# base.net
KiCad netlist of a schematic drawn in EAGLE
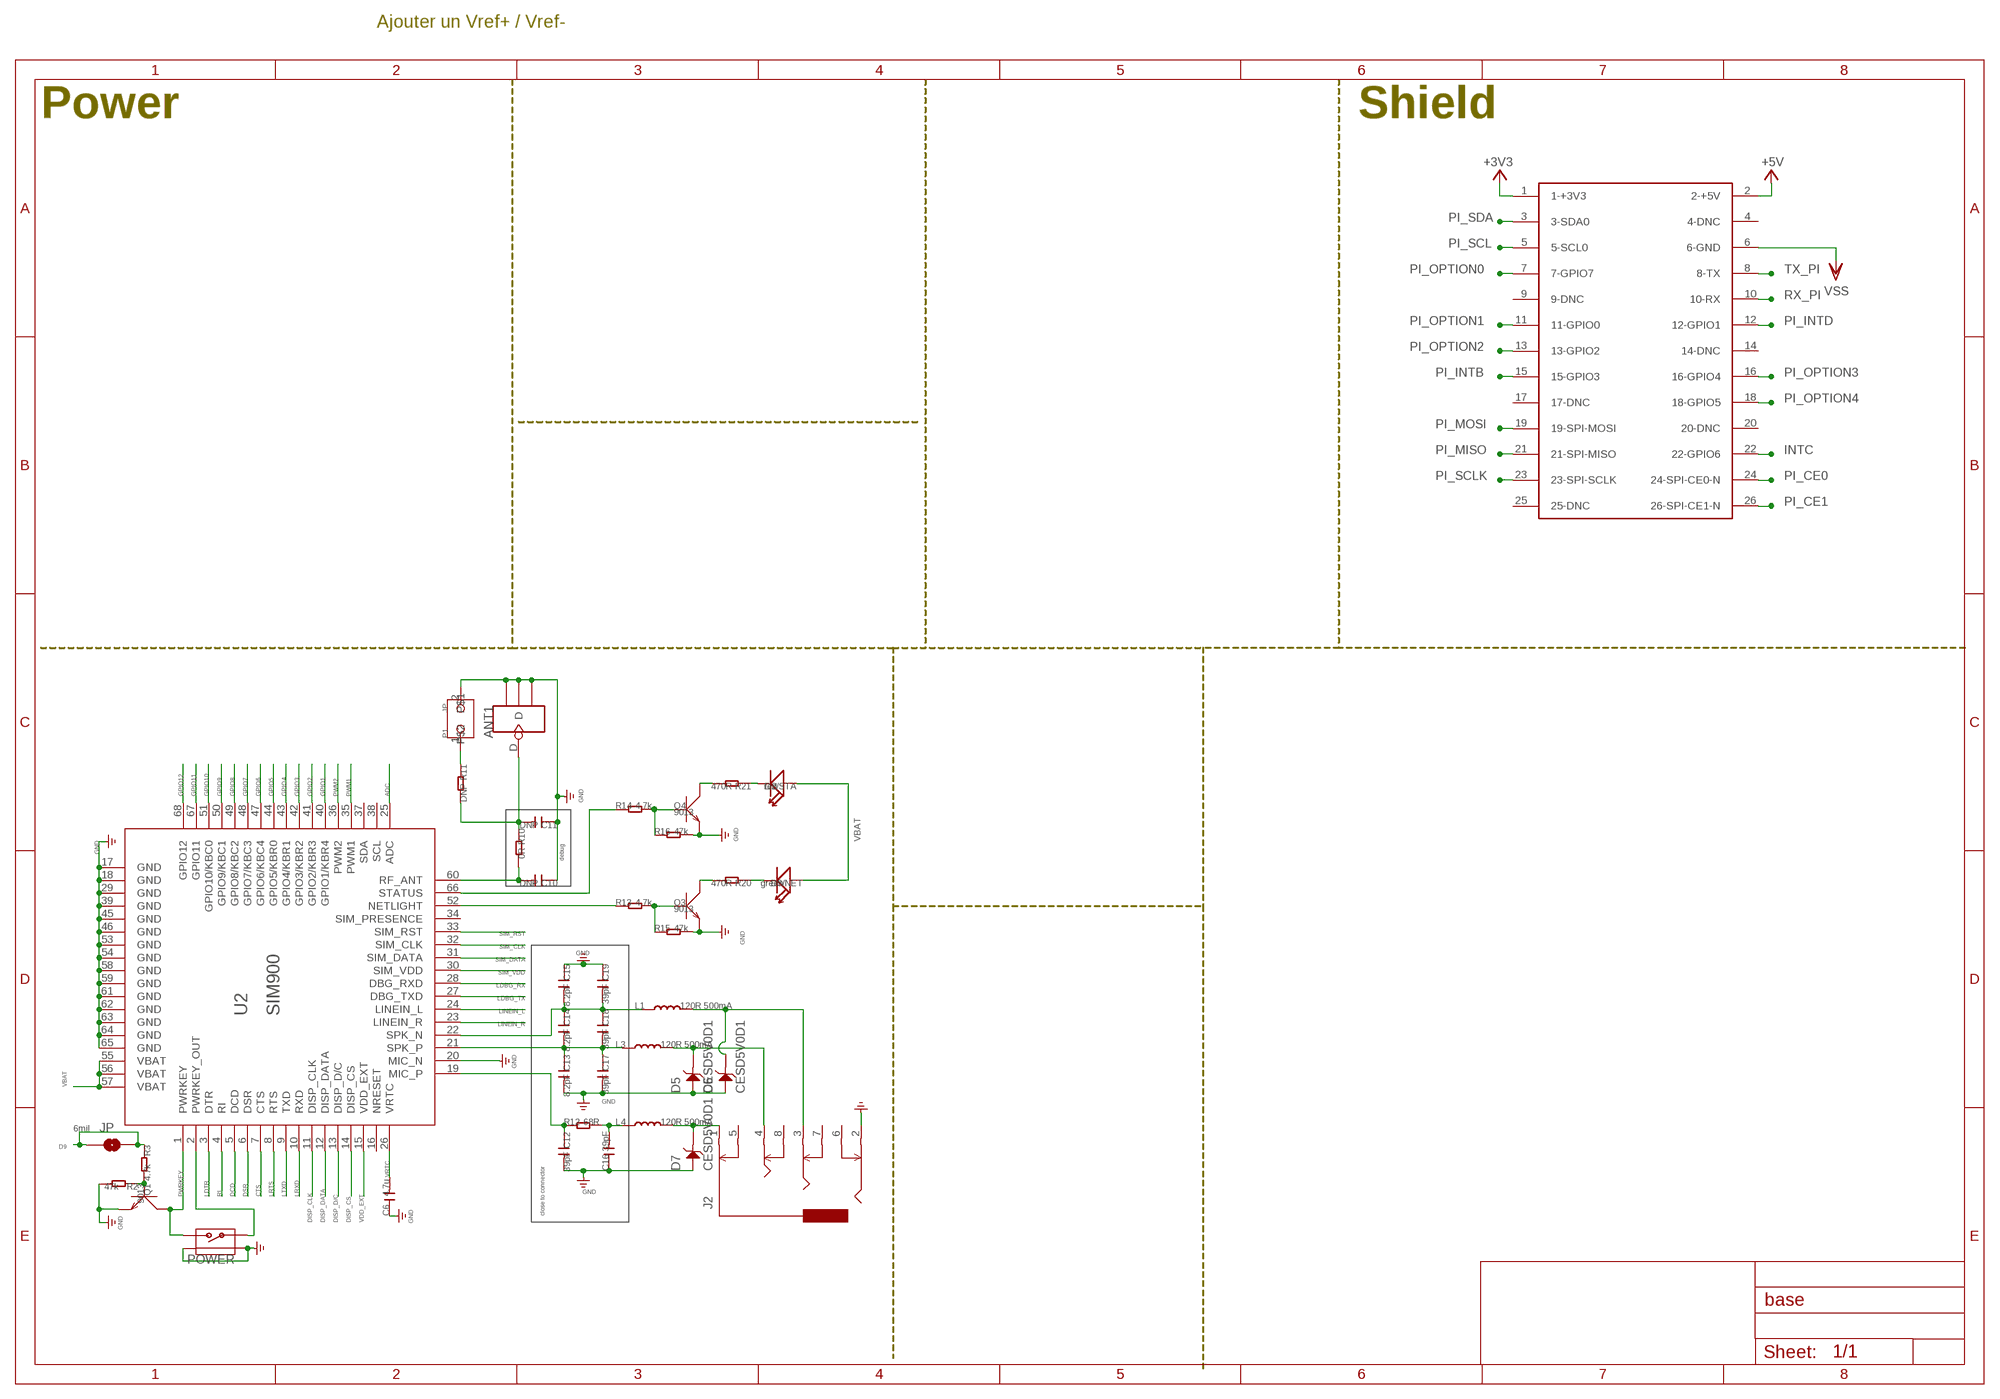
[diagram p0: schematic, sheet 1]

(export (version "E")
  (design (tool "Eeschema 10.0.6"))
  (components
    (comp (ref "ANT1")
      (value "ANTENNA-U-FL")
      (footprint "eagle-import:4P-U-FL")
      (libsource (lib "eagle-import") (part "ANTENNA-U-FL"))
    )
    (comp (ref "C6")
      (value "4.7u")
      (footprint "eagle-import:C0805")
      (libsource (lib "eagle-import") (part "C-0805"))
    )
    (comp (ref "C10")
      (value "DNP")
      (footprint "eagle-import:C0603")
      (libsource (lib "eagle-import") (part "C-0603"))
    )
    (comp (ref "C11")
      (value "DNP")
      (footprint "eagle-import:C0603")
      (libsource (lib "eagle-import") (part "C-0603"))
    )
    (comp (ref "C12")
      (value "39pF")
      (footprint "eagle-import:C0603")
      (libsource (lib "eagle-import") (part "C-0603"))
    )
    (comp (ref "C13")
      (value "8.2pF")
      (footprint "eagle-import:C0603")
      (libsource (lib "eagle-import") (part "C-0603"))
    )
    (comp (ref "C14")
      (value "8.2pF")
      (footprint "eagle-import:C0603")
      (libsource (lib "eagle-import") (part "C-0603"))
    )
    (comp (ref "C15")
      (value "8.2pF")
      (footprint "eagle-import:C0603")
      (libsource (lib "eagle-import") (part "C-0603"))
    )
    (comp (ref "C16")
      (value "39pF")
      (footprint "eagle-import:C0603")
      (libsource (lib "eagle-import") (part "C-0603"))
    )
    (comp (ref "C17")
      (value "39pF")
      (footprint "eagle-import:C0603")
      (libsource (lib "eagle-import") (part "C-0603"))
    )
    (comp (ref "C18")
      (value "39pF")
      (footprint "eagle-import:C0603")
      (libsource (lib "eagle-import") (part "C-0603"))
    )
    (comp (ref "C19")
      (value "39pF")
      (footprint "eagle-import:C0603")
      (libsource (lib "eagle-import") (part "C-0603"))
    )
    (comp (ref "D2/STA")
      (value "red")
      (footprint "eagle-import:LED-0603")
      (libsource (lib "eagle-import") (part "LED'0603'"))
    )
    (comp (ref "D3/NET")
      (value "green")
      (footprint "eagle-import:LED-0603")
      (libsource (lib "eagle-import") (part "LED'0603'"))
    )
    (comp (ref "D5")
      (value "CESD5V0D1")
      (footprint "eagle-import:SOD123-2.7X1.6")
      (libsource (lib "eagle-import") (part "D-ESD"))
    )
    (comp (ref "D6")
      (value "CESD5V0D1")
      (footprint "eagle-import:SOD123-2.7X1.6")
      (libsource (lib "eagle-import") (part "D-ESD"))
    )
    (comp (ref "D7")
      (value "CESD5V0D1")
      (footprint "eagle-import:SOD123-2.7X1.6")
      (libsource (lib "eagle-import") (part "D-ESD"))
    )
    (comp (ref "J2")
      (value "AUDIO-8P'PJ-3536-L6S'")
      (footprint "eagle-import:8P-3.5-SMD")
      (libsource (lib "eagle-import") (part "AUDIO-8P'PJ-3536-L6S'"))
    )
    (comp (ref "JP")
      (value "PAD-SOLDERJUMPERNC")
      (footprint "eagle-import:2P-SMD-3.3X2")
      (libsource (lib "eagle-import") (part "PAD-SOLDERJUMPERNC"))
    )
    (comp (ref "L1")
      (value "120R 500mA")
      (footprint "eagle-import:L0603")
      (libsource (lib "eagle-import") (part "L'0603'"))
    )
    (comp (ref "L3")
      (value "120R 500mA")
      (footprint "eagle-import:L0603")
      (libsource (lib "eagle-import") (part "L'0603'"))
    )
    (comp (ref "L4")
      (value "120R 500mA")
      (footprint "eagle-import:L0603")
      (libsource (lib "eagle-import") (part "L'0603'"))
    )
    (comp (ref "P1") (value "JP") (footprint "eagle-import:JP") (libsource (lib "eagle-import") (part "JP")))
    (comp (ref "POWER")
      (value "BUTTON-4P-REINFORCE'TS-118E'")
      (footprint "eagle-import:4P-SMD-7X3.5X3.5H")
      (libsource (lib "eagle-import") (part "BUTTON-4P-REINFORCE'TS-118E'"))
    )
    (comp (ref "Q1")
      (value "9013")
      (footprint "eagle-import:SOT23")
      (libsource (lib "eagle-import") (part "TRANSISTOR-NPN-SOT23"))
    )
    (comp (ref "Q3")
      (value "9013")
      (footprint "eagle-import:SOT23")
      (libsource (lib "eagle-import") (part "TRANSISTOR-NPN-SOT23"))
    )
    (comp (ref "Q4")
      (value "9013")
      (footprint "eagle-import:SOT23")
      (libsource (lib "eagle-import") (part "TRANSISTOR-NPN-SOT23"))
    )
    (comp (ref "R2")
      (value "47k")
      (footprint "eagle-import:R0603")
      (libsource (lib "eagle-import") (part "R-0603"))
    )
    (comp (ref "R3")
      (value "4.7k")
      (footprint "eagle-import:R0603")
      (libsource (lib "eagle-import") (part "R-0603"))
    )
    (comp (ref "R10")
      (value "0R")
      (footprint "eagle-import:R0603")
      (libsource (lib "eagle-import") (part "R-0603"))
    )
    (comp (ref "R11")
      (value "DNP")
      (footprint "eagle-import:R0603")
      (libsource (lib "eagle-import") (part "R-0603"))
    )
    (comp (ref "R12")
      (value "68R")
      (footprint "eagle-import:R0603")
      (libsource (lib "eagle-import") (part "R-0603"))
    )
    (comp (ref "R13")
      (value "4.7k")
      (footprint "eagle-import:R0603")
      (libsource (lib "eagle-import") (part "R-0603"))
    )
    (comp (ref "R14")
      (value "4.7k")
      (footprint "eagle-import:R0603")
      (libsource (lib "eagle-import") (part "R-0603"))
    )
    (comp (ref "R15")
      (value "47k")
      (footprint "eagle-import:R0603")
      (libsource (lib "eagle-import") (part "R-0603"))
    )
    (comp (ref "R16")
      (value "47k")
      (footprint "eagle-import:R0603")
      (libsource (lib "eagle-import") (part "R-0603"))
    )
    (comp (ref "R20")
      (value "470R")
      (footprint "eagle-import:R0603")
      (libsource (lib "eagle-import") (part "R-0603"))
    )
    (comp (ref "R21")
      (value "470R")
      (footprint "eagle-import:R0603")
      (libsource (lib "eagle-import") (part "R-0603"))
    )
    (comp (ref "U$3")
      (value "RASPBERRY-PILIGHT-HOLE")
      (footprint "eagle-import:RASPBERRY-PI-LIGHT-HOLE")
      (libsource (lib "eagle-import") (part "RASPBERRY-PILIGHT-HOLE"))
    )
    (comp (ref "U2")
      (value "SIM900")
      (footprint "eagle-import:SIM900")
      (libsource (lib "eagle-import") (part "SIM900"))
    )
  )
  (nets
    (net (code "1") (name "+3V3") (class "Default")
      (node (ref "U$3") (pin "1") (pinfunction "1-+3V3_1") (pintype "bidirectional"))
    )
    (net (code "2") (name "+5V") (class "Default")
      (node (ref "U$3") (pin "2") (pinfunction "2-+5V_2") (pintype "bidirectional"))
    )
    (net (code "3") (name "/ADC") (class "Default")
      (node (ref "U2") (pin "25") (pinfunction "ADC_25") (pintype "input"))
    )
    (net (code "4") (name "/CTS") (class "Default")
      (node (ref "U2") (pin "7") (pinfunction "CTS_7") (pintype "output"))
    )
    (net (code "5") (name "/D9") (class "Default")
      (node (ref "JP") (pin "1") (pinfunction "1_1") (pintype "passive"))
      (node (ref "JP") (pin "2") (pinfunction "2_2") (pintype "passive"))
      (node (ref "R3") (pin "1") (pinfunction "1_1") (pintype "passive"))
    )
    (net (code "6") (name "/DCD") (class "Default")
      (node (ref "U2") (pin "5") (pinfunction "DCD_5") (pintype "output"))
    )
    (net (code "7") (name "/DISP_CLK") (class "Default")
      (node (ref "U2") (pin "11") (pinfunction "DISP_CLK_11") (pintype "output"))
    )
    (net (code "8") (name "/DISP_CS") (class "Default")
      (node (ref "U2") (pin "14") (pinfunction "DISP_CS_14") (pintype "output"))
    )
    (net (code "9") (name "/DISP_DATA") (class "Default")
      (node (ref "U2") (pin "12") (pinfunction "DISP_DATA_12") (pintype "bidirectional"))
    )
    (net (code "10") (name "/DISP_D{slash}C") (class "Default")
      (node (ref "U2") (pin "13") (pinfunction "DISP_D/C_13") (pintype "output"))
    )
    (net (code "11") (name "/DSR") (class "Default")
      (node (ref "U2") (pin "6") (pinfunction "DSR_6") (pintype "output"))
    )
    (net (code "12") (name "/GPIO1") (class "Default")
      (node (ref "U2") (pin "40") (pinfunction "GPIO1/KBR4_40") (pintype "output"))
    )
    (net (code "13") (name "/GPIO2") (class "Default")
      (node (ref "U2") (pin "41") (pinfunction "GPIO2/KBR3_41") (pintype "output"))
    )
    (net (code "14") (name "/GPIO3") (class "Default")
      (node (ref "U2") (pin "42") (pinfunction "GPIO3/KBR2_42") (pintype "output"))
    )
    (net (code "15") (name "/GPIO4") (class "Default")
      (node (ref "U2") (pin "43") (pinfunction "GPIO4/KBR1_43") (pintype "output"))
    )
    (net (code "16") (name "/GPIO5") (class "Default")
      (node (ref "U2") (pin "44") (pinfunction "GPIO5/KBR0_44") (pintype "output"))
    )
    (net (code "17") (name "/GPIO6") (class "Default")
      (node (ref "U2") (pin "47") (pinfunction "GPIO6/KBC4_47") (pintype "input"))
    )
    (net (code "18") (name "/GPIO7") (class "Default")
      (node (ref "U2") (pin "48") (pinfunction "GPIO7/KBC3_48") (pintype "bidirectional"))
    )
    (net (code "19") (name "/GPIO8") (class "Default")
      (node (ref "U2") (pin "49") (pinfunction "GPIO8/KBC2_49") (pintype "input"))
    )
    (net (code "20") (name "/GPIO9") (class "Default")
      (node (ref "U2") (pin "50") (pinfunction "GPIO9/KBC1_50") (pintype "input"))
    )
    (net (code "21") (name "/GPIO10") (class "Default")
      (node (ref "U2") (pin "51") (pinfunction "GPIO10/KBC0_51") (pintype "bidirectional"))
    )
    (net (code "22") (name "/GPIO11") (class "Default")
      (node (ref "U2") (pin "67") (pinfunction "GPIO11_67") (pintype "bidirectional"))
    )
    (net (code "23") (name "/GPIO12") (class "Default")
      (node (ref "U2") (pin "68") (pinfunction "GPIO12_68") (pintype "bidirectional"))
    )
    (net (code "24") (name "/INTC") (class "Default")
      (node (ref "U$3") (pin "22") (pinfunction "22-GPIO6_22") (pintype "bidirectional"))
    )
    (net (code "25") (name "/LDBG_RX") (class "Default")
      (node (ref "U2") (pin "28") (pinfunction "DBG_RXD_28") (pintype "input"))
    )
    (net (code "26") (name "/LDBG_TX") (class "Default")
      (node (ref "U2") (pin "27") (pinfunction "DBG_TXD_27") (pintype "output"))
    )
    (net (code "27") (name "/LDTR") (class "Default")
      (node (ref "U2") (pin "3") (pinfunction "DTR_3") (pintype "input"))
    )
    (net (code "28") (name "/LINEIN_L") (class "Default")
      (node (ref "U2") (pin "24") (pinfunction "LINEIN_L_24") (pintype "input"))
    )
    (net (code "29") (name "/LINEIN_R") (class "Default")
      (node (ref "U2") (pin "23") (pinfunction "LINEIN_R_23") (pintype "input"))
    )
    (net (code "30") (name "/LRTS") (class "Default")
      (node (ref "U2") (pin "8") (pinfunction "RTS_8") (pintype "input"))
    )
    (net (code "31") (name "/LRXD") (class "Default")
      (node (ref "U2") (pin "10") (pinfunction "RXD_10") (pintype "input"))
    )
    (net (code "32") (name "/LTXD") (class "Default")
      (node (ref "U2") (pin "9") (pinfunction "TXD_9") (pintype "output"))
    )
    (net (code "33") (name "/PI_CE0") (class "Default")
      (node (ref "U$3") (pin "24") (pinfunction "24-SPI-CE0-N_24") (pintype "bidirectional"))
    )
    (net (code "34") (name "/PI_CE1") (class "Default")
      (node (ref "U$3") (pin "26") (pinfunction "26-SPI-CE1-N_26") (pintype "bidirectional"))
    )
    (net (code "35") (name "/PI_INTB") (class "Default")
      (node (ref "U$3") (pin "15") (pinfunction "15-GPIO3_15") (pintype "bidirectional"))
    )
    (net (code "36") (name "/PI_INTD") (class "Default")
      (node (ref "U$3") (pin "12") (pinfunction "12-GPIO1_12") (pintype "bidirectional"))
    )
    (net (code "37") (name "/PI_MISO") (class "Default")
      (node (ref "U$3") (pin "21") (pinfunction "21-SPI-MISO_21") (pintype "bidirectional"))
    )
    (net (code "38") (name "/PI_MOSI") (class "Default")
      (node (ref "U$3") (pin "19") (pinfunction "19-SPI-MOSI_19") (pintype "bidirectional"))
    )
    (net (code "39") (name "/PI_OPTION0") (class "Default")
      (node (ref "U$3") (pin "7") (pinfunction "7-GPIO7_7") (pintype "bidirectional"))
    )
    (net (code "40") (name "/PI_OPTION1") (class "Default")
      (node (ref "U$3") (pin "11") (pinfunction "11-GPIO0_11") (pintype "bidirectional"))
    )
    (net (code "41") (name "/PI_OPTION2") (class "Default")
      (node (ref "U$3") (pin "13") (pinfunction "13-GPIO2_13") (pintype "bidirectional"))
    )
    (net (code "42") (name "/PI_OPTION3") (class "Default")
      (node (ref "U$3") (pin "16") (pinfunction "16-GPIO4_16") (pintype "bidirectional"))
    )
    (net (code "43") (name "/PI_OPTION4") (class "Default")
      (node (ref "U$3") (pin "18") (pinfunction "18-GPIO5_18") (pintype "bidirectional"))
    )
    (net (code "44") (name "/PI_SCL") (class "Default")
      (node (ref "U$3") (pin "5") (pinfunction "5-SCL0_5") (pintype "bidirectional"))
    )
    (net (code "45") (name "/PI_SCLK") (class "Default")
      (node (ref "U$3") (pin "23") (pinfunction "23-SPI-SCLK_23") (pintype "bidirectional"))
    )
    (net (code "46") (name "/PI_SDA") (class "Default")
      (node (ref "U$3") (pin "3") (pinfunction "3-SDA0_3") (pintype "bidirectional"))
    )
    (net (code "47") (name "/PWM1") (class "Default")
      (node (ref "U2") (pin "35") (pinfunction "PWM1_35") (pintype "output"))
    )
    (net (code "48") (name "/PWM2") (class "Default")
      (node (ref "U2") (pin "36") (pinfunction "PWM2_36") (pintype "output"))
    )
    (net (code "49") (name "/PWRKEY") (class "Default")
      (node (ref "POWER") (pin "2") (pinfunction "2_2") (pintype "bidirectional"))
      (node (ref "Q1") (pin "3") (pinfunction "C_3") (pintype "passive"))
      (node (ref "U2") (pin "1") (pinfunction "PWRKEY_1") (pintype "input"))
    )
    (net (code "50") (name "/RI") (class "Default")
      (node (ref "U2") (pin "4") (pinfunction "RI_4") (pintype "output"))
    )
    (net (code "51") (name "/RX_PI") (class "Default")
      (node (ref "U$3") (pin "10") (pinfunction "10-RX_10") (pintype "bidirectional"))
    )
    (net (code "52") (name "/SIM_CLK") (class "Default")
      (node (ref "U2") (pin "32") (pinfunction "SIM_CLK_32") (pintype "output"))
    )
    (net (code "53") (name "/SIM_DATA") (class "Default")
      (node (ref "U2") (pin "31") (pinfunction "SIM_DATA_31") (pintype "bidirectional"))
    )
    (net (code "54") (name "/SIM_RST") (class "Default")
      (node (ref "U2") (pin "33") (pinfunction "SIM_RST_33") (pintype "output"))
    )
    (net (code "55") (name "/SIM_VDD") (class "Default")
      (node (ref "U2") (pin "30") (pinfunction "SIM_VDD_30") (pintype "output"))
    )
    (net (code "56") (name "/TX_PI") (class "Default")
      (node (ref "U$3") (pin "8") (pinfunction "8-TX_8") (pintype "bidirectional"))
    )
    (net (code "57") (name "/VBAT") (class "Default")
      (node (ref "D2/STA") (pin "+") (pinfunction "+_+") (pintype "passive"))
      (node (ref "D3/NET") (pin "+") (pinfunction "+_+") (pintype "passive"))
      (node (ref "U2") (pin "55") (pinfunction "VBAT_55") (pintype "power_in"))
      (node (ref "U2") (pin "56") (pinfunction "VBAT_56") (pintype "power_in"))
      (node (ref "U2") (pin "57") (pinfunction "VBAT_57") (pintype "power_in"))
    )
    (net (code "58") (name "/VDD_EXT") (class "Default")
      (node (ref "U2") (pin "15") (pinfunction "VDD_EXT_15") (pintype "output"))
    )
    (net (code "59") (name "/VRTC") (class "Default")
      (node (ref "C6") (pin "2") (pinfunction "2_2") (pintype "passive"))
      (node (ref "U2") (pin "26") (pinfunction "VRTC_26") (pintype "bidirectional"))
    )
    (net (code "60") (name "GND_POWER") (class "Default")
      (node (ref "ANT1") (pin "GND1") (pinfunction "GND1_GND1") (pintype "bidirectional"))
      (node (ref "ANT1") (pin "GND2") (pinfunction "GND2_GND2") (pintype "bidirectional"))
      (node (ref "ANT1") (pin "GND3") (pinfunction "GND3_GND3") (pintype "bidirectional"))
      (node (ref "C10") (pin "1") (pinfunction "1_1") (pintype "passive"))
      (node (ref "C11") (pin "1") (pinfunction "1_1") (pintype "passive"))
      (node (ref "C12") (pin "2") (pinfunction "2_2") (pintype "passive"))
      (node (ref "C13") (pin "2") (pinfunction "2_2") (pintype "passive"))
      (node (ref "C15") (pin "1") (pinfunction "1_1") (pintype "passive"))
      (node (ref "C16") (pin "1") (pinfunction "1_1") (pintype "passive"))
      (node (ref "C17") (pin "2") (pinfunction "2_2") (pintype "passive"))
      (node (ref "C19") (pin "1") (pinfunction "1_1") (pintype "passive"))
      (node (ref "C6") (pin "1") (pinfunction "1_1") (pintype "passive"))
      (node (ref "D5") (pin "1") (pinfunction "1_1") (pintype "bidirectional"))
      (node (ref "D6") (pin "1") (pinfunction "1_1") (pintype "bidirectional"))
      (node (ref "D7") (pin "1") (pinfunction "1_1") (pintype "bidirectional"))
      (node (ref "J2") (pin "2") (pinfunction "2_2") (pintype "bidirectional"))
      (node (ref "P1") (pin "2") (pinfunction "P$2_2") (pintype "bidirectional"))
      (node (ref "POWER") (pin "S1") (pinfunction "S1_S1") (pintype "bidirectional"))
      (node (ref "POWER") (pin "S2") (pinfunction "S2_S2") (pintype "bidirectional"))
      (node (ref "Q1") (pin "2") (pinfunction "E_2") (pintype "passive"))
      (node (ref "Q3") (pin "2") (pinfunction "E_2") (pintype "passive"))
      (node (ref "Q4") (pin "2") (pinfunction "E_2") (pintype "passive"))
      (node (ref "R15") (pin "2") (pinfunction "2_2") (pintype "passive"))
      (node (ref "R16") (pin "2") (pinfunction "2_2") (pintype "passive"))
      (node (ref "R2") (pin "2") (pinfunction "2_2") (pintype "passive"))
      (node (ref "U2") (pin "17") (pinfunction "GND_17") (pintype "power_in"))
      (node (ref "U2") (pin "18") (pinfunction "GND_18") (pintype "power_in"))
      (node (ref "U2") (pin "20") (pinfunction "MIC_N_20") (pintype "input"))
      (node (ref "U2") (pin "29") (pinfunction "GND_29") (pintype "power_in"))
      (node (ref "U2") (pin "39") (pinfunction "GND_39") (pintype "power_in"))
      (node (ref "U2") (pin "45") (pinfunction "GND_45") (pintype "power_in"))
      (node (ref "U2") (pin "46") (pinfunction "GND_46") (pintype "power_in"))
      (node (ref "U2") (pin "53") (pinfunction "GND_53") (pintype "power_in"))
      (node (ref "U2") (pin "54") (pinfunction "GND_54") (pintype "power_in"))
      (node (ref "U2") (pin "58") (pinfunction "GND_58") (pintype "power_in"))
      (node (ref "U2") (pin "59") (pinfunction "GND_59") (pintype "power_in"))
      (node (ref "U2") (pin "61") (pinfunction "GND_61") (pintype "power_in"))
      (node (ref "U2") (pin "62") (pinfunction "GND_62") (pintype "power_in"))
      (node (ref "U2") (pin "63") (pinfunction "GND_63") (pintype "power_in"))
      (node (ref "U2") (pin "64") (pinfunction "GND_64") (pintype "power_in"))
      (node (ref "U2") (pin "65") (pinfunction "GND_65") (pintype "power_in"))
    )
    (net (code "61") (name "Net-(ANT1-PadD)") (class "Default")
      (node (ref "ANT1") (pin "D") (pinfunction "D_D") (pintype "bidirectional"))
      (node (ref "C11") (pin "2") (pinfunction "2_2") (pintype "passive"))
      (node (ref "R10") (pin "1") (pinfunction "1_1") (pintype "passive"))
      (node (ref "R11") (pin "2") (pinfunction "2_2") (pintype "passive"))
    )
    (net (code "62") (name "Net-(C16-Pad2)") (class "Default")
      (node (ref "C16") (pin "2") (pinfunction "2_2") (pintype "passive"))
      (node (ref "L4") (pin "1") (pinfunction "1_1") (pintype "passive"))
      (node (ref "R12") (pin "2") (pinfunction "2_2") (pintype "passive"))
    )
    (net (code "63") (name "Net-(D2/STA-Pad-)") (class "Default")
      (node (ref "D2/STA") (pin "-") (pinfunction "-_-") (pintype "passive"))
      (node (ref "R21") (pin "1") (pinfunction "1_1") (pintype "passive"))
    )
    (net (code "64") (name "Net-(D3/NET-Pad-)") (class "Default")
      (node (ref "D3/NET") (pin "-") (pinfunction "-_-") (pintype "passive"))
      (node (ref "R20") (pin "1") (pinfunction "1_1") (pintype "passive"))
    )
    (net (code "65") (name "Net-(D5-Pad2)") (class "Default")
      (node (ref "D5") (pin "2") (pinfunction "2_2") (pintype "bidirectional"))
      (node (ref "J2") (pin "4") (pinfunction "4_4") (pintype "bidirectional"))
      (node (ref "L3") (pin "2") (pinfunction "2_2") (pintype "passive"))
    )
    (net (code "66") (name "Net-(D6-Pad2)") (class "Default")
      (node (ref "D6") (pin "2") (pinfunction "2_2") (pintype "bidirectional"))
      (node (ref "J2") (pin "3") (pinfunction "3_3") (pintype "bidirectional"))
      (node (ref "L1") (pin "2") (pinfunction "2_2") (pintype "passive"))
    )
    (net (code "67") (name "Net-(D7-Pad2)") (class "Default")
      (node (ref "D7") (pin "2") (pinfunction "2_2") (pintype "bidirectional"))
      (node (ref "J2") (pin "1") (pinfunction "1_1") (pintype "bidirectional"))
      (node (ref "L4") (pin "2") (pinfunction "2_2") (pintype "passive"))
    )
    (net (code "68") (name "Net-(P1-P$1)") (class "Default")
      (node (ref "P1") (pin "1") (pinfunction "P$1_1") (pintype "bidirectional"))
      (node (ref "R11") (pin "1") (pinfunction "1_1") (pintype "passive"))
    )
    (net (code "69") (name "Net-(Q1-B)") (class "Default")
      (node (ref "Q1") (pin "1") (pinfunction "B_1") (pintype "passive"))
      (node (ref "R2") (pin "1") (pinfunction "1_1") (pintype "passive"))
      (node (ref "R3") (pin "2") (pinfunction "2_2") (pintype "passive"))
    )
    (net (code "70") (name "Net-(Q3-B)") (class "Default")
      (node (ref "Q3") (pin "1") (pinfunction "B_1") (pintype "passive"))
      (node (ref "R13") (pin "2") (pinfunction "2_2") (pintype "passive"))
      (node (ref "R15") (pin "1") (pinfunction "1_1") (pintype "passive"))
    )
    (net (code "71") (name "Net-(Q3-C)") (class "Default")
      (node (ref "Q3") (pin "3") (pinfunction "C_3") (pintype "passive"))
      (node (ref "R20") (pin "2") (pinfunction "2_2") (pintype "passive"))
    )
    (net (code "72") (name "Net-(Q4-B)") (class "Default")
      (node (ref "Q4") (pin "1") (pinfunction "B_1") (pintype "passive"))
      (node (ref "R14") (pin "2") (pinfunction "2_2") (pintype "passive"))
      (node (ref "R16") (pin "1") (pinfunction "1_1") (pintype "passive"))
    )
    (net (code "73") (name "Net-(Q4-C)") (class "Default")
      (node (ref "Q4") (pin "3") (pinfunction "C_3") (pintype "passive"))
      (node (ref "R21") (pin "2") (pinfunction "2_2") (pintype "passive"))
    )
    (net (code "74") (name "Net-(U2-MIC_P)") (class "Default")
      (node (ref "C12") (pin "1") (pinfunction "1_1") (pintype "passive"))
      (node (ref "R12") (pin "1") (pinfunction "1_1") (pintype "passive"))
      (node (ref "U2") (pin "19") (pinfunction "MIC_P_19") (pintype "input"))
    )
    (net (code "75") (name "Net-(U2-NETLIGHT)") (class "Default")
      (node (ref "R13") (pin "1") (pinfunction "1_1") (pintype "passive"))
      (node (ref "U2") (pin "52") (pinfunction "NETLIGHT_52") (pintype "output"))
    )
    (net (code "76") (name "Net-(U2-PWRKEY_OUT)") (class "Default")
      (node (ref "POWER") (pin "1") (pinfunction "1_1") (pintype "bidirectional"))
      (node (ref "U2") (pin "2") (pinfunction "PWRKEY_OUT_2") (pintype "output"))
    )
    (net (code "77") (name "Net-(U2-RF_ANT)") (class "Default")
      (node (ref "C10") (pin "2") (pinfunction "2_2") (pintype "passive"))
      (node (ref "R10") (pin "2") (pinfunction "2_2") (pintype "passive"))
      (node (ref "U2") (pin "60") (pinfunction "RF_ANT_60") (pintype "bidirectional"))
    )
    (net (code "78") (name "Net-(U2-SPK_N)") (class "Default")
      (node (ref "C14") (pin "1") (pinfunction "1_1") (pintype "passive"))
      (node (ref "C15") (pin "2") (pinfunction "2_2") (pintype "passive"))
      (node (ref "C18") (pin "1") (pinfunction "1_1") (pintype "passive"))
      (node (ref "C19") (pin "2") (pinfunction "2_2") (pintype "passive"))
      (node (ref "L1") (pin "1") (pinfunction "1_1") (pintype "passive"))
      (node (ref "U2") (pin "22") (pinfunction "SPK_N_22") (pintype "output"))
    )
    (net (code "79") (name "Net-(U2-SPK_P)") (class "Default")
      (node (ref "C13") (pin "1") (pinfunction "1_1") (pintype "passive"))
      (node (ref "C14") (pin "2") (pinfunction "2_2") (pintype "passive"))
      (node (ref "C17") (pin "1") (pinfunction "1_1") (pintype "passive"))
      (node (ref "C18") (pin "2") (pinfunction "2_2") (pintype "passive"))
      (node (ref "L3") (pin "1") (pinfunction "1_1") (pintype "passive"))
      (node (ref "U2") (pin "21") (pinfunction "SPK_P_21") (pintype "output"))
    )
    (net (code "80") (name "Net-(U2-STATUS)") (class "Default")
      (node (ref "R14") (pin "1") (pinfunction "1_1") (pintype "passive"))
      (node (ref "U2") (pin "66") (pinfunction "STATUS_66") (pintype "output"))
    )
    (net (code "81") (name "VSS") (class "Default")
      (node (ref "U$3") (pin "6") (pinfunction "6-GND_6") (pintype "bidirectional"))
    )
    (net (code "82") (name "unconnected-(J2-Pad5)") (class "Default")
      (node (ref "J2") (pin "5") (pinfunction "5_5") (pintype "bidirectional"))
    )
    (net (code "83") (name "unconnected-(J2-Pad6)") (class "Default")
      (node (ref "J2") (pin "6") (pinfunction "6_6") (pintype "bidirectional"))
    )
    (net (code "84") (name "unconnected-(J2-Pad7)") (class "Default")
      (node (ref "J2") (pin "7") (pinfunction "7_7") (pintype "bidirectional"))
    )
    (net (code "85") (name "unconnected-(J2-Pad8)") (class "Default")
      (node (ref "J2") (pin "8") (pinfunction "8_8") (pintype "bidirectional"))
    )
    (net (code "86") (name "unconnected-(U$3-4-DNC-Pad4)") (class "Default")
      (node (ref "U$3") (pin "4") (pinfunction "4-DNC_4") (pintype "bidirectional"))
    )
    (net (code "87") (name "unconnected-(U$3-9-DNC-Pad9)") (class "Default")
      (node (ref "U$3") (pin "9") (pinfunction "9-DNC_9") (pintype "bidirectional"))
    )
    (net (code "88") (name "unconnected-(U$3-14-DNC-Pad14)") (class "Default")
      (node (ref "U$3") (pin "14") (pinfunction "14-DNC_14") (pintype "bidirectional"))
    )
    (net (code "89") (name "unconnected-(U$3-17-DNC-Pad17)") (class "Default")
      (node (ref "U$3") (pin "17") (pinfunction "17-DNC_17") (pintype "bidirectional"))
    )
    (net (code "90") (name "unconnected-(U$3-20-DNC-Pad20)") (class "Default")
      (node (ref "U$3") (pin "20") (pinfunction "20-DNC_20") (pintype "bidirectional"))
    )
    (net (code "91") (name "unconnected-(U$3-25-DNC-Pad25)") (class "Default")
      (node (ref "U$3") (pin "25") (pinfunction "25-DNC_25") (pintype "bidirectional"))
    )
    (net (code "92") (name "unconnected-(U2-NRESET-Pad16)") (class "Default")
      (node (ref "U2") (pin "16") (pinfunction "NRESET_16") (pintype "input"))
    )
    (net (code "93") (name "unconnected-(U2-SCL-Pad38)") (class "Default")
      (node (ref "U2") (pin "38") (pinfunction "SCL_38") (pintype "output"))
    )
    (net (code "94") (name "unconnected-(U2-SDA-Pad37)") (class "Default")
      (node (ref "U2") (pin "37") (pinfunction "SDA_37") (pintype "bidirectional"))
    )
    (net (code "95") (name "unconnected-(U2-SIM_PRESENCE-Pad34)") (class "Default")
      (node (ref "U2") (pin "34") (pinfunction "SIM_PRESENCE_34") (pintype "input"))
    )
  )
)
